# Filters_n_Buffers.net
KiCad netlist of a schematic drawn in Altium Designer
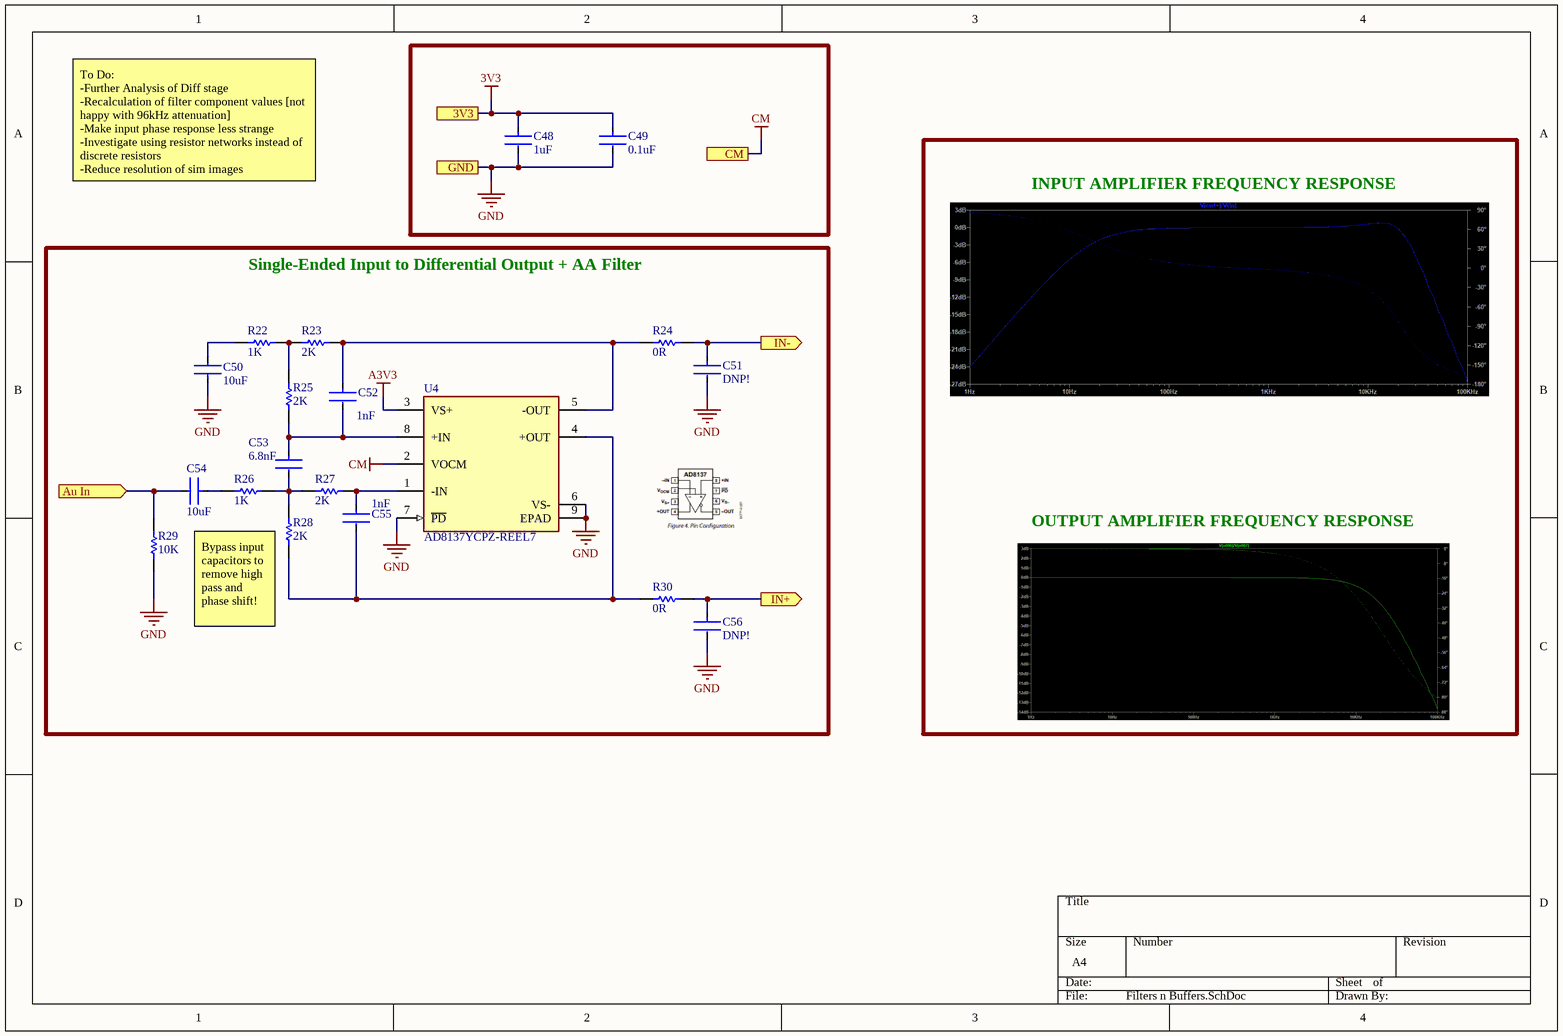
[diagram p0: Filters n Buffers.SchDoc]

(export (version "E")
  (design (tool "Eeschema 10.0.6"))
  (components
    (comp (ref "C48")
      (value "1uF")
      (footprint "FP-GRM15-MFG")
      (description "CAP CER 0.1UF 16V X7R 0402")
      (fields (field (name "MANUFACTURER PART NUMBER") "GRM155R71C104KA88D") (field (name "TOLERANCE") "10%"))
      (libsource (lib "Altium Content Vault") (part "236180d848d6139a670b325ea6854c9"))
    )
    (comp (ref "C49")
      (value "0.1uF")
      (footprint "FP-GRM15-MFG")
      (description "CAP CER 0.1UF 16V X7R 0402")
      (fields (field (name "MANUFACTURER PART NUMBER") "GRM155R71C104KA88D") (field (name "TOLERANCE") "10%"))
      (libsource (lib "Altium Content Vault") (part "236180d848d6139a670b325ea6854c9"))
    )
    (comp (ref "C50")
      (value "10uF")
      (footprint "FP-GRM15-MFG")
      (description "CAP CER 0.1UF 16V X7R 0402")
      (fields (field (name "MANUFACTURER PART NUMBER") "GRM155R71C104KA88D") (field (name "TOLERANCE") "10%"))
      (libsource (lib "Altium Content Vault") (part "236180d848d6139a670b325ea6854c9"))
    )
    (comp (ref "C51")
      (value "DNP!")
      (footprint "FP-GRM15-MFG")
      (description "CAP CER 0.1UF 16V X7R 0402")
      (fields (field (name "MANUFACTURER PART NUMBER") "GRM155R71C104KA88D") (field (name "TOLERANCE") "10%"))
      (libsource (lib "Altium Content Vault") (part "236180d848d6139a670b325ea6854c9"))
    )
    (comp (ref "C52")
      (value "1nF")
      (footprint "FP-GRM15-MFG")
      (description "CAP CER 0.1UF 16V X7R 0402")
      (fields (field (name "MANUFACTURER PART NUMBER") "GRM155R71C104KA88D") (field (name "TOLERANCE") "10%"))
      (libsource (lib "Altium Content Vault") (part "236180d848d6139a670b325ea6854c9"))
    )
    (comp (ref "C53")
      (value "6.8nF")
      (footprint "FP-GRM15-MFG")
      (description "CAP CER 0.1UF 16V X7R 0402")
      (fields (field (name "MANUFACTURER PART NUMBER") "GRM155R71C104KA88D") (field (name "TOLERANCE") "10%"))
      (libsource (lib "Altium Content Vault") (part "236180d848d6139a670b325ea6854c9"))
    )
    (comp (ref "C54")
      (value "10uF")
      (footprint "FP-GRM15-MFG")
      (description "CAP CER 0.1UF 16V X7R 0402")
      (fields (field (name "MANUFACTURER PART NUMBER") "GRM155R71C104KA88D") (field (name "TOLERANCE") "10%"))
      (libsource (lib "Altium Content Vault") (part "236180d848d6139a670b325ea6854c9"))
    )
    (comp (ref "C55")
      (value "1nF")
      (footprint "FP-GRM15-MFG")
      (description "CAP CER 0.1UF 16V X7R 0402")
      (fields (field (name "MANUFACTURER PART NUMBER") "GRM155R71C104KA88D") (field (name "TOLERANCE") "10%"))
      (libsource (lib "Altium Content Vault") (part "236180d848d6139a670b325ea6854c9"))
    )
    (comp (ref "C56")
      (value "DNP!")
      (footprint "FP-GRM15-MFG")
      (description "CAP CER 0.1UF 16V X7R 0402")
      (fields (field (name "MANUFACTURER PART NUMBER") "GRM155R71C104KA88D") (field (name "TOLERANCE") "10%"))
      (libsource (lib "Altium Content Vault") (part "236180d848d6139a670b325ea6854c9"))
    )
    (comp (ref "R22")
      (value "1K")
      (footprint "RESC1005X40X25LL05T05")
      (description "Chip Resistor, 0 Ohm, 0.1 W, -55 to 155 degC, 0402 (1005 Metric), RoHS, Tape and Reel")
      (fields (field (name "MANUFACTURER") "Panasonic") (field (name "TOLERANCE") "5%"))
      (libsource (lib "Altium Content Vault") (part "RES-2"))
    )
    (comp (ref "R23")
      (value "2K")
      (footprint "RESC1005X40X25LL05T05")
      (description "Chip Resistor, 0 Ohm, 0.1 W, -55 to 155 degC, 0402 (1005 Metric), RoHS, Tape and Reel")
      (fields (field (name "MANUFACTURER") "Panasonic") (field (name "TOLERANCE") "5%"))
      (libsource (lib "Altium Content Vault") (part "RES-2"))
    )
    (comp (ref "R24")
      (value "0R")
      (footprint "RESC1005X40X25LL05T05")
      (description "Chip Resistor, 0 Ohm, 0.1 W, -55 to 155 degC, 0402 (1005 Metric), RoHS, Tape and Reel")
      (fields (field (name "MANUFACTURER") "Panasonic") (field (name "TOLERANCE") "5%"))
      (libsource (lib "Altium Content Vault") (part "RES-2"))
    )
    (comp (ref "R25")
      (value "2K")
      (footprint "RESC1005X40X25LL05T05")
      (description "Chip Resistor, 0 Ohm, 0.1 W, -55 to 155 degC, 0402 (1005 Metric), RoHS, Tape and Reel")
      (fields (field (name "MANUFACTURER") "Panasonic") (field (name "TOLERANCE") "5%"))
      (libsource (lib "Altium Content Vault") (part "RES-2"))
    )
    (comp (ref "R26")
      (value "1K")
      (footprint "RESC1005X40X25LL05T05")
      (description "Chip Resistor, 0 Ohm, 0.1 W, -55 to 155 degC, 0402 (1005 Metric), RoHS, Tape and Reel")
      (fields (field (name "MANUFACTURER") "Panasonic") (field (name "TOLERANCE") "5%"))
      (libsource (lib "Altium Content Vault") (part "RES-2"))
    )
    (comp (ref "R27")
      (value "2K")
      (footprint "RESC1005X40X25LL05T05")
      (description "Chip Resistor, 0 Ohm, 0.1 W, -55 to 155 degC, 0402 (1005 Metric), RoHS, Tape and Reel")
      (fields (field (name "MANUFACTURER") "Panasonic") (field (name "TOLERANCE") "5%"))
      (libsource (lib "Altium Content Vault") (part "RES-2"))
    )
    (comp (ref "R28")
      (value "2K")
      (footprint "RESC1005X40X25LL05T05")
      (description "Chip Resistor, 0 Ohm, 0.1 W, -55 to 155 degC, 0402 (1005 Metric), RoHS, Tape and Reel")
      (fields (field (name "MANUFACTURER") "Panasonic") (field (name "TOLERANCE") "5%"))
      (libsource (lib "Altium Content Vault") (part "RES-2"))
    )
    (comp (ref "R29")
      (value "10K")
      (footprint "RESC1005X40X25LL05T05")
      (description "Chip Resistor, 0 Ohm, 0.1 W, -55 to 155 degC, 0402 (1005 Metric), RoHS, Tape and Reel")
      (fields (field (name "MANUFACTURER") "Panasonic") (field (name "TOLERANCE") "5%"))
      (libsource (lib "Altium Content Vault") (part "RES-2"))
    )
    (comp (ref "R30")
      (value "0R")
      (footprint "RESC1005X40X25LL05T05")
      (description "Chip Resistor, 0 Ohm, 0.1 W, -55 to 155 degC, 0402 (1005 Metric), RoHS, Tape and Reel")
      (fields (field (name "MANUFACTURER") "Panasonic") (field (name "TOLERANCE") "5%"))
      (libsource (lib "Altium Content Vault") (part "RES-2"))
    )
    (comp (ref "U4")
      (value "AD8137YCPZ-REEL7")
      (footprint "FP-CP-8-13-IPC_C")
      (description "IC OPAMP DIFF 1 CIRCUIT 8LFCSP")
      (libsource (lib "Altium Content Vault") (part "b3a67ab1d6d60b00f57058e55bbdee4"))
    )
  )
  (nets
    (net (code "1") (name "/Au In") (class "Default")
      (node (ref "C54") (pin "1") (pinfunction "1_1") (pintype "passive"))
      (node (ref "R29") (pin "1") (pinfunction "1_1") (pintype "passive"))
    )
    (net (code "2") (name "/IN+") (class "Default")
      (node (ref "C56") (pin "2") (pinfunction "2_2") (pintype "passive"))
      (node (ref "R30") (pin "2") (pinfunction "2_2") (pintype "passive"))
    )
    (net (code "3") (name "/IN-") (class "Default")
      (node (ref "C51") (pin "2") (pinfunction "2_2") (pintype "passive"))
      (node (ref "R24") (pin "2") (pinfunction "2_2") (pintype "passive"))
    )
    (net (code "4") (name "3V3") (class "Default")
      (node (ref "C48") (pin "2") (pinfunction "2_2") (pintype "passive"))
      (node (ref "C49") (pin "2") (pinfunction "2_2") (pintype "passive"))
    )
    (net (code "5") (name "A3V3") (class "Default")
      (node (ref "U4") (pin "3") (pinfunction "VS+_3") (pintype "power_in"))
    )
    (net (code "6") (name "CM") (class "Default")
      (node (ref "U4") (pin "2") (pinfunction "VOCM_2") (pintype "passive"))
    )
    (net (code "7") (name "GND") (class "Default")
      (node (ref "C48") (pin "1") (pinfunction "1_1") (pintype "passive"))
      (node (ref "C49") (pin "1") (pinfunction "1_1") (pintype "passive"))
      (node (ref "C50") (pin "2") (pinfunction "2_2") (pintype "passive"))
      (node (ref "C51") (pin "1") (pinfunction "1_1") (pintype "passive"))
      (node (ref "C56") (pin "1") (pinfunction "1_1") (pintype "passive"))
      (node (ref "R29") (pin "2") (pinfunction "2_2") (pintype "passive"))
      (node (ref "U4") (pin "6") (pinfunction "VS-_6") (pintype "power_in"))
      (node (ref "U4") (pin "7") (pinfunction "~{PD}_7") (pintype "input"))
      (node (ref "U4") (pin "9") (pinfunction "EPAD_9") (pintype "power_in"))
    )
    (net (code "8") (name "Net-(C50-Pad1)") (class "Default")
      (node (ref "C50") (pin "1") (pinfunction "1_1") (pintype "passive"))
      (node (ref "R22") (pin "1") (pinfunction "1_1") (pintype "passive"))
    )
    (net (code "9") (name "Net-(C53-Pad1)") (class "Default")
      (node (ref "C53") (pin "1") (pinfunction "1_1") (pintype "passive"))
      (node (ref "R26") (pin "2") (pinfunction "2_2") (pintype "passive"))
      (node (ref "R27") (pin "1") (pinfunction "1_1") (pintype "passive"))
      (node (ref "R28") (pin "2") (pinfunction "2_2") (pintype "passive"))
    )
    (net (code "10") (name "Net-(C54-Pad2)") (class "Default")
      (node (ref "C54") (pin "2") (pinfunction "2_2") (pintype "passive"))
      (node (ref "R26") (pin "1") (pinfunction "1_1") (pintype "passive"))
    )
    (net (code "11") (name "Net-(R22-Pad2)") (class "Default")
      (node (ref "R22") (pin "2") (pinfunction "2_2") (pintype "passive"))
      (node (ref "R23") (pin "1") (pinfunction "1_1") (pintype "passive"))
      (node (ref "R25") (pin "2") (pinfunction "2_2") (pintype "passive"))
    )
    (net (code "12") (name "Net-(U4-+IN)") (class "Default")
      (node (ref "C52") (pin "1") (pinfunction "1_1") (pintype "passive"))
      (node (ref "C53") (pin "2") (pinfunction "2_2") (pintype "passive"))
      (node (ref "R25") (pin "1") (pinfunction "1_1") (pintype "passive"))
      (node (ref "U4") (pin "8") (pinfunction "+IN_8") (pintype "tri_state"))
    )
    (net (code "13") (name "Net-(U4-+OUT)") (class "Default")
      (node (ref "C55") (pin "1") (pinfunction "1_1") (pintype "passive"))
      (node (ref "R28") (pin "1") (pinfunction "1_1") (pintype "passive"))
      (node (ref "R30") (pin "1") (pinfunction "1_1") (pintype "passive"))
      (node (ref "U4") (pin "4") (pinfunction "+OUT_4") (pintype "passive"))
    )
    (net (code "14") (name "Net-(U4--IN)") (class "Default")
      (node (ref "C55") (pin "2") (pinfunction "2_2") (pintype "passive"))
      (node (ref "R27") (pin "2") (pinfunction "2_2") (pintype "passive"))
      (node (ref "U4") (pin "1") (pinfunction "-IN_1") (pintype "tri_state"))
    )
    (net (code "15") (name "Net-(U4--OUT)") (class "Default")
      (node (ref "C52") (pin "2") (pinfunction "2_2") (pintype "passive"))
      (node (ref "R23") (pin "2") (pinfunction "2_2") (pintype "passive"))
      (node (ref "R24") (pin "1") (pinfunction "1_1") (pintype "passive"))
      (node (ref "U4") (pin "5") (pinfunction "-OUT_5") (pintype "passive"))
    )
  )
)
